# knitic_sol_connect_kh970.net
KiCad netlist of a schematic drawn in EAGLE
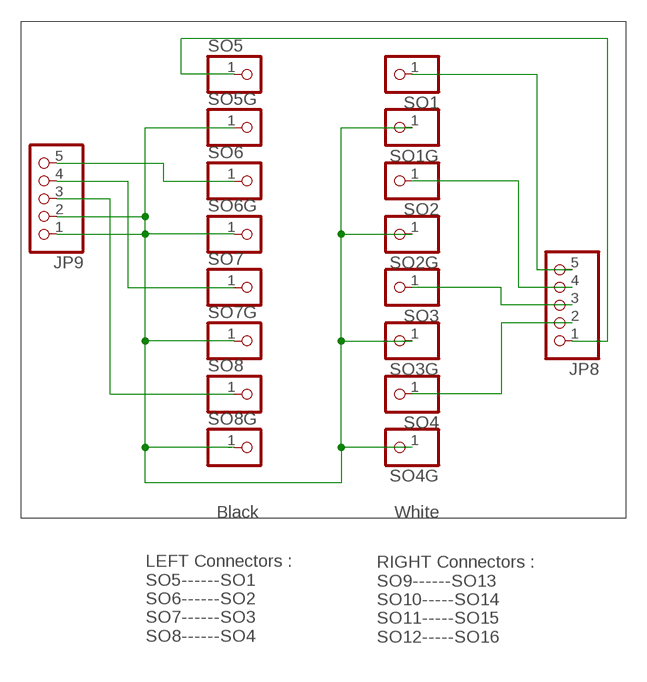
[diagram p0: schematic, sheet 1]

(export (version "E")
  (design (tool "Eeschema 10.0.6"))
  (components
    (comp (ref "JP8")
      (value "PINHD-1X5")
      (footprint "eagle-import:1X05")
      (libsource (lib "eagle-import") (part "PINHD-1X5"))
    )
    (comp (ref "JP9")
      (value "PINHD-1X5")
      (footprint "eagle-import:1X05")
      (libsource (lib "eagle-import") (part "PINHD-1X5"))
    )
    (comp (ref "SO1")
      (value "PINHD-1X1")
      (footprint "eagle-import:1X01")
      (libsource (lib "eagle-import") (part "PINHD-1X1"))
    )
    (comp (ref "SO1G")
      (value "PINHD-1X1")
      (footprint "eagle-import:1X01")
      (libsource (lib "eagle-import") (part "PINHD-1X1"))
    )
    (comp (ref "SO2")
      (value "PINHD-1X1")
      (footprint "eagle-import:1X01")
      (libsource (lib "eagle-import") (part "PINHD-1X1"))
    )
    (comp (ref "SO2G")
      (value "PINHD-1X1")
      (footprint "eagle-import:1X01")
      (libsource (lib "eagle-import") (part "PINHD-1X1"))
    )
    (comp (ref "SO3")
      (value "PINHD-1X1")
      (footprint "eagle-import:1X01")
      (libsource (lib "eagle-import") (part "PINHD-1X1"))
    )
    (comp (ref "SO3G")
      (value "PINHD-1X1")
      (footprint "eagle-import:1X01")
      (libsource (lib "eagle-import") (part "PINHD-1X1"))
    )
    (comp (ref "SO4")
      (value "PINHD-1X1")
      (footprint "eagle-import:1X01")
      (libsource (lib "eagle-import") (part "PINHD-1X1"))
    )
    (comp (ref "SO4G")
      (value "PINHD-1X1")
      (footprint "eagle-import:1X01")
      (libsource (lib "eagle-import") (part "PINHD-1X1"))
    )
    (comp (ref "SO5")
      (value "PINHD-1X1")
      (footprint "eagle-import:1X01")
      (libsource (lib "eagle-import") (part "PINHD-1X1"))
    )
    (comp (ref "SO5G")
      (value "PINHD-1X1")
      (footprint "eagle-import:1X01")
      (libsource (lib "eagle-import") (part "PINHD-1X1"))
    )
    (comp (ref "SO6")
      (value "PINHD-1X1")
      (footprint "eagle-import:1X01")
      (libsource (lib "eagle-import") (part "PINHD-1X1"))
    )
    (comp (ref "SO6G")
      (value "PINHD-1X1")
      (footprint "eagle-import:1X01")
      (libsource (lib "eagle-import") (part "PINHD-1X1"))
    )
    (comp (ref "SO7")
      (value "PINHD-1X1")
      (footprint "eagle-import:1X01")
      (libsource (lib "eagle-import") (part "PINHD-1X1"))
    )
    (comp (ref "SO7G")
      (value "PINHD-1X1")
      (footprint "eagle-import:1X01")
      (libsource (lib "eagle-import") (part "PINHD-1X1"))
    )
    (comp (ref "SO8")
      (value "PINHD-1X1")
      (footprint "eagle-import:1X01")
      (libsource (lib "eagle-import") (part "PINHD-1X1"))
    )
    (comp (ref "SO8G")
      (value "PINHD-1X1")
      (footprint "eagle-import:1X01")
      (libsource (lib "eagle-import") (part "PINHD-1X1"))
    )
  )
  (nets
    (net (code "1") (name "Net-(JP8-Pad1)") (class "Default")
      (node (ref "JP8") (pin "1") (pinfunction "1_1") (pintype "passive"))
      (node (ref "SO5") (pin "1") (pinfunction "1_1") (pintype "passive"))
    )
    (net (code "2") (name "Net-(JP8-Pad2)") (class "Default")
      (node (ref "JP8") (pin "2") (pinfunction "2_2") (pintype "passive"))
      (node (ref "SO4") (pin "1") (pinfunction "1_1") (pintype "passive"))
    )
    (net (code "3") (name "Net-(JP8-Pad3)") (class "Default")
      (node (ref "JP8") (pin "3") (pinfunction "3_3") (pintype "passive"))
      (node (ref "SO3") (pin "1") (pinfunction "1_1") (pintype "passive"))
    )
    (net (code "4") (name "Net-(JP8-Pad4)") (class "Default")
      (node (ref "JP8") (pin "4") (pinfunction "4_4") (pintype "passive"))
      (node (ref "SO2") (pin "1") (pinfunction "1_1") (pintype "passive"))
    )
    (net (code "5") (name "Net-(JP8-Pad5)") (class "Default")
      (node (ref "JP8") (pin "5") (pinfunction "5_5") (pintype "passive"))
      (node (ref "SO1") (pin "1") (pinfunction "1_1") (pintype "passive"))
    )
    (net (code "6") (name "Net-(JP9-Pad1)") (class "Default")
      (node (ref "JP9") (pin "1") (pinfunction "1_1") (pintype "passive"))
      (node (ref "JP9") (pin "2") (pinfunction "2_2") (pintype "passive"))
      (node (ref "SO1G") (pin "1") (pinfunction "1_1") (pintype "passive"))
      (node (ref "SO2G") (pin "1") (pinfunction "1_1") (pintype "passive"))
      (node (ref "SO3G") (pin "1") (pinfunction "1_1") (pintype "passive"))
      (node (ref "SO4G") (pin "1") (pinfunction "1_1") (pintype "passive"))
      (node (ref "SO5G") (pin "1") (pinfunction "1_1") (pintype "passive"))
      (node (ref "SO6G") (pin "1") (pinfunction "1_1") (pintype "passive"))
      (node (ref "SO7G") (pin "1") (pinfunction "1_1") (pintype "passive"))
      (node (ref "SO8G") (pin "1") (pinfunction "1_1") (pintype "passive"))
    )
    (net (code "7") (name "Net-(JP9-Pad3)") (class "Default")
      (node (ref "JP9") (pin "3") (pinfunction "3_3") (pintype "passive"))
      (node (ref "SO8") (pin "1") (pinfunction "1_1") (pintype "passive"))
    )
    (net (code "8") (name "Net-(JP9-Pad4)") (class "Default")
      (node (ref "JP9") (pin "4") (pinfunction "4_4") (pintype "passive"))
      (node (ref "SO7") (pin "1") (pinfunction "1_1") (pintype "passive"))
    )
    (net (code "9") (name "Net-(JP9-Pad5)") (class "Default")
      (node (ref "JP9") (pin "5") (pinfunction "5_5") (pintype "passive"))
      (node (ref "SO6") (pin "1") (pinfunction "1_1") (pintype "passive"))
    )
  )
)
